# Image_sensor.net
KiCad netlist of a schematic drawn in EasyEDA Pro
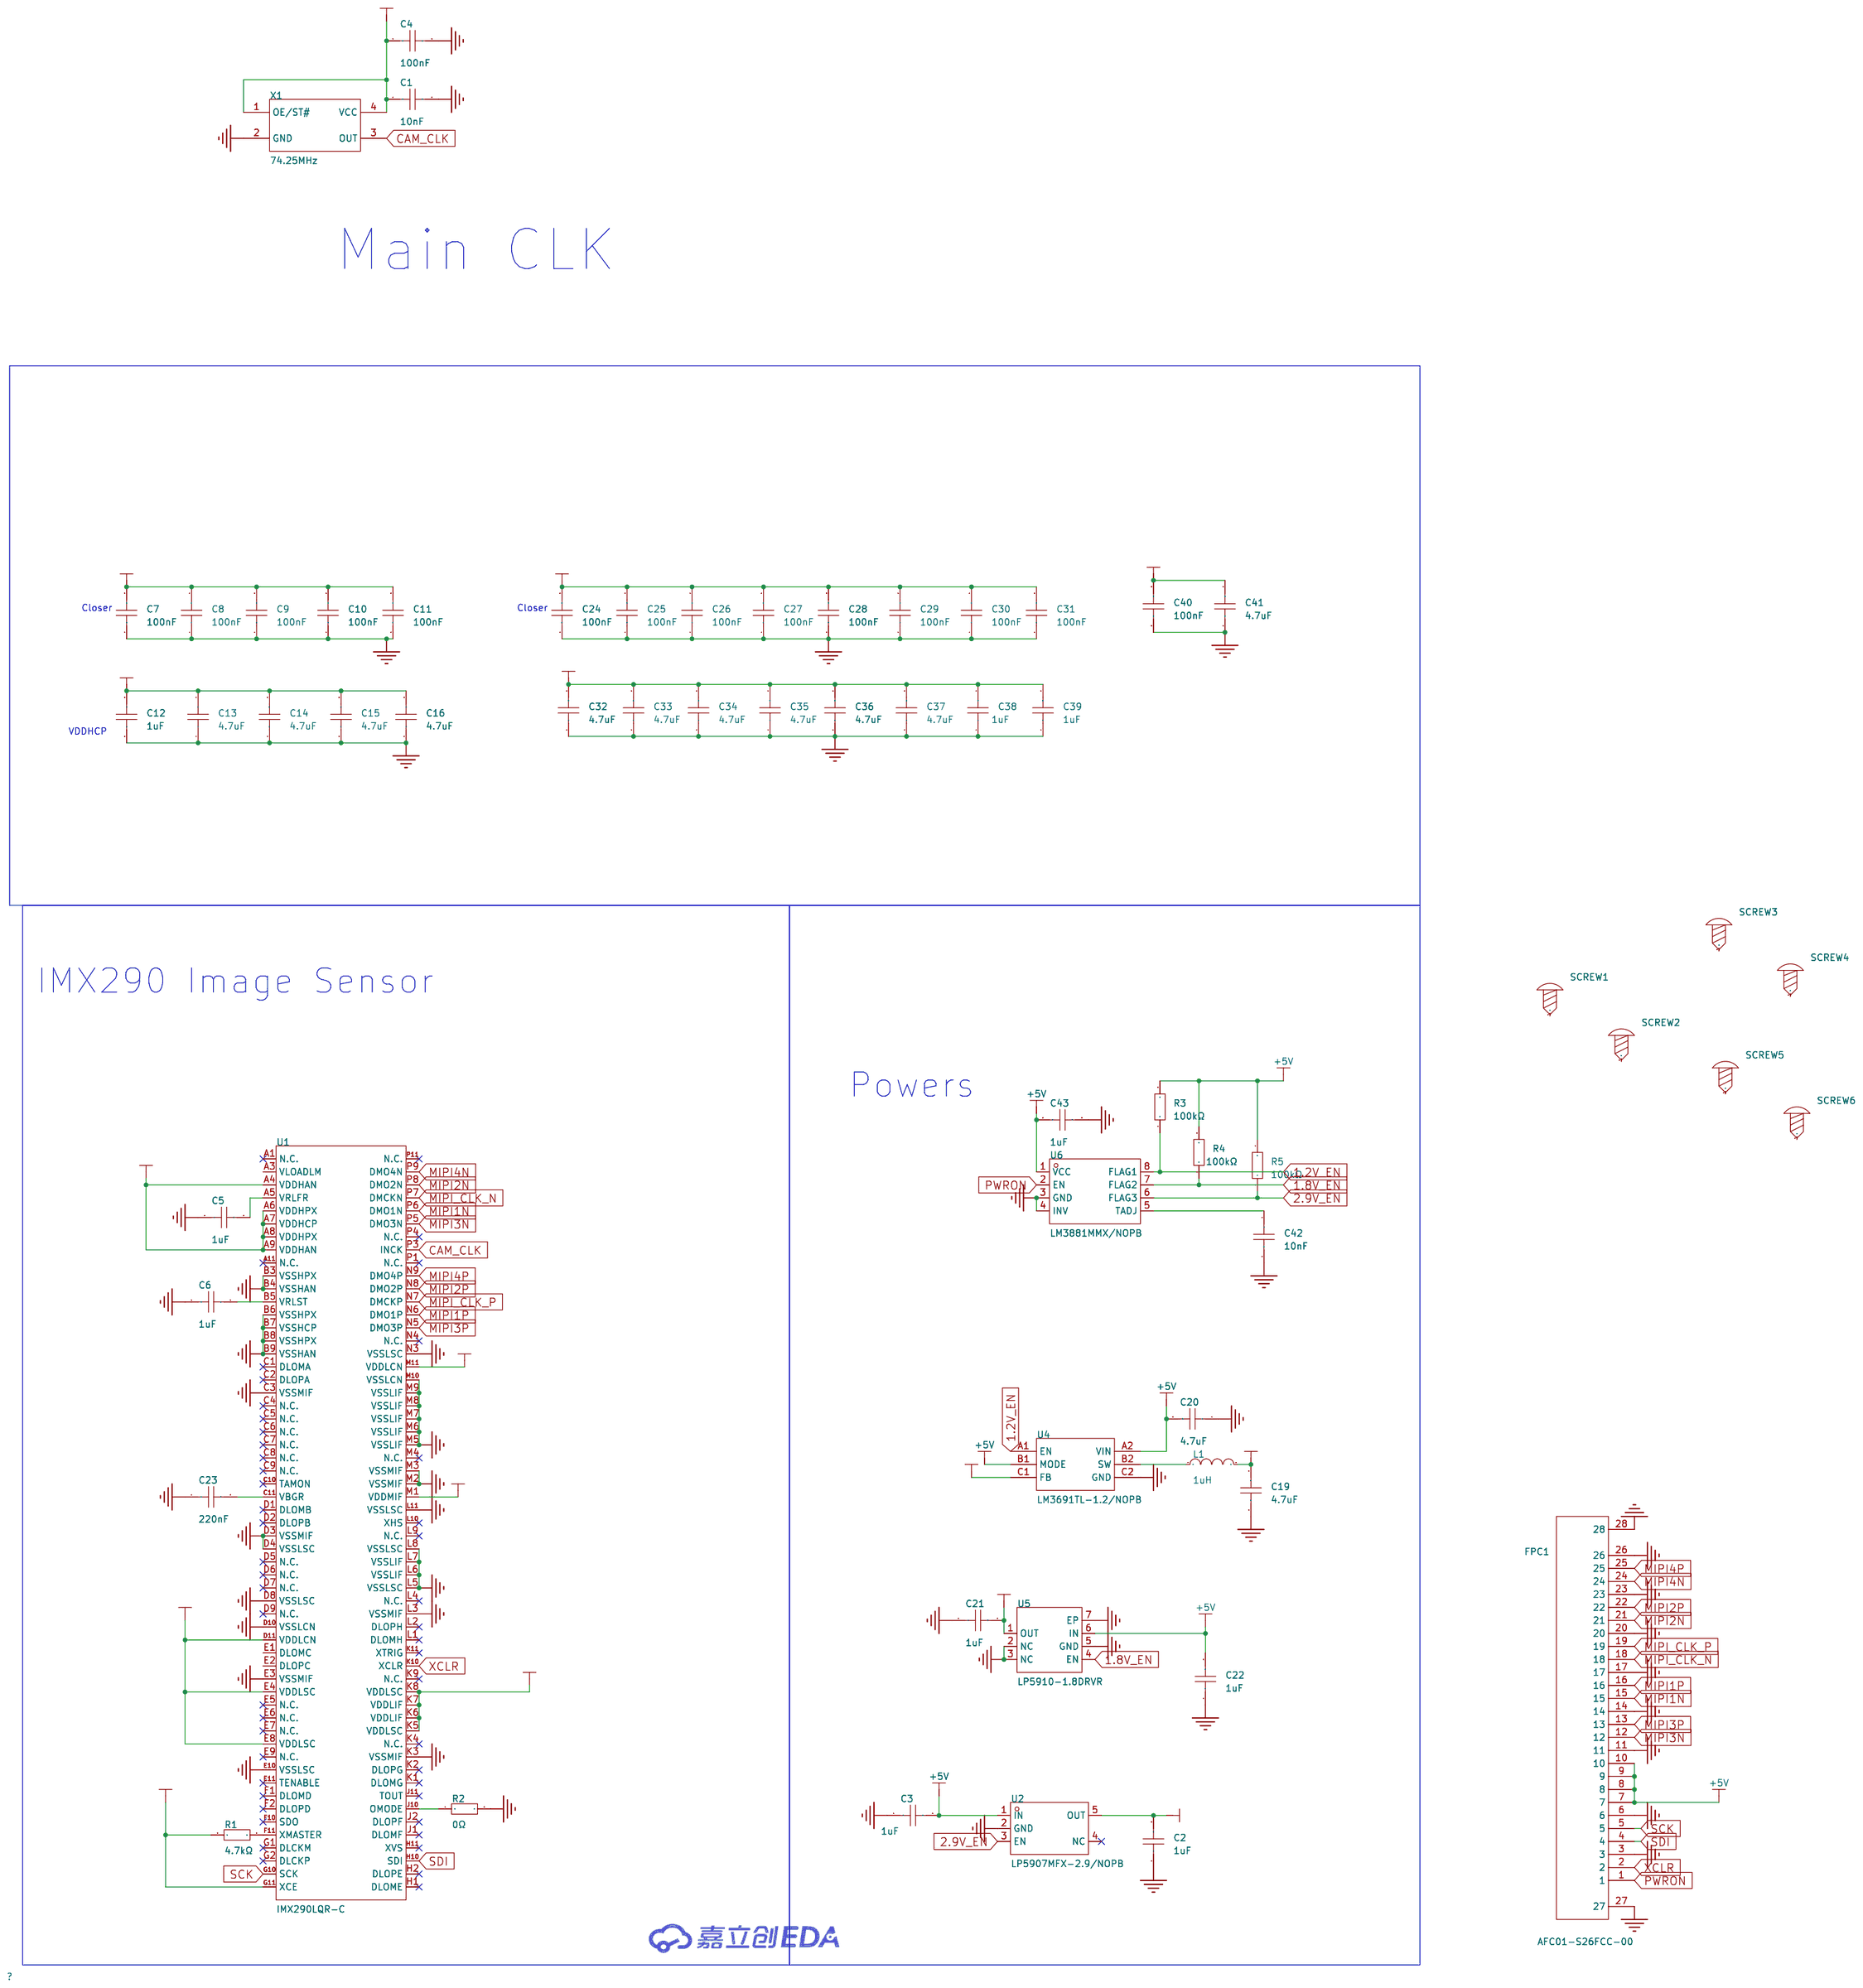
[diagram p0: schematic sheet]

(export (version "E")
  (design (tool "Eeschema 10.0.6"))
  (components
    (comp (ref "C1")
      (value "10nF")
      (footprint "easyedapro:C0603")
      (fields
        (field (name "Manufacturer Part") "CL02A103KQ2NNXC")
        (field (name "Manufacturer") "SAMSUNG(三星)")
      )
      (libsource (lib "easyedapro") (part "Capacitance"))
    )
    (comp (ref "C2")
      (value "1uF")
      (footprint "easyedapro:C0603")
      (fields
        (field (name "Manufacturer Part") "CL03A105KP3NSNC")
        (field (name "Manufacturer") "SAMSUNG(三星)")
      )
      (libsource (lib "easyedapro") (part "Capacitance"))
    )
    (comp (ref "C3")
      (value "1uF")
      (footprint "easyedapro:C0603")
      (fields
        (field (name "Manufacturer Part") "CL03A105KP3NSNC")
        (field (name "Manufacturer") "SAMSUNG(三星)")
      )
      (libsource (lib "easyedapro") (part "Capacitance"))
    )
    (comp (ref "C4")
      (value "100nF")
      (footprint "easyedapro:C0603")
      (fields
        (field (name "Manufacturer Part") "GRM022R60J104KE15D")
        (field (name "Manufacturer") "muRata(村田)")
      )
      (libsource (lib "easyedapro") (part "Capacitance"))
    )
    (comp (ref "C5")
      (value "1uF")
      (footprint "easyedapro:C0603")
      (fields
        (field (name "Manufacturer Part") "CL03A105KP3NSNC")
        (field (name "Manufacturer") "SAMSUNG(三星)")
      )
      (libsource (lib "easyedapro") (part "Capacitance"))
    )
    (comp (ref "C6")
      (value "1uF")
      (footprint "easyedapro:C0603")
      (fields
        (field (name "Manufacturer Part") "CL03A105KP3NSNC")
        (field (name "Manufacturer") "SAMSUNG(三星)")
      )
      (libsource (lib "easyedapro") (part "Capacitance"))
    )
    (comp (ref "C7")
      (value "100nF")
      (footprint "easyedapro:C0603")
      (fields
        (field (name "Manufacturer Part") "GRM022R60J104KE15D")
        (field (name "Manufacturer") "muRata(村田)")
      )
      (libsource (lib "easyedapro") (part "Capacitance"))
    )
    (comp (ref "C8")
      (value "100nF")
      (footprint "easyedapro:C0603")
      (fields
        (field (name "Manufacturer Part") "GRM022R60J104KE15D")
        (field (name "Manufacturer") "muRata(村田)")
      )
      (libsource (lib "easyedapro") (part "Capacitance"))
    )
    (comp (ref "C9")
      (value "100nF")
      (footprint "easyedapro:C0603")
      (fields
        (field (name "Manufacturer Part") "GRM022R60J104KE15D")
        (field (name "Manufacturer") "muRata(村田)")
      )
      (libsource (lib "easyedapro") (part "Capacitance"))
    )
    (comp (ref "C10")
      (value "100nF")
      (footprint "easyedapro:C0603")
      (fields
        (field (name "Manufacturer Part") "GRM022R60J104KE15D")
        (field (name "Manufacturer") "muRata(村田)")
      )
      (libsource (lib "easyedapro") (part "Capacitance"))
    )
    (comp (ref "C11")
      (value "100nF")
      (footprint "easyedapro:C0603")
      (fields
        (field (name "Manufacturer Part") "GRM022R60J104KE15D")
        (field (name "Manufacturer") "muRata(村田)")
      )
      (libsource (lib "easyedapro") (part "Capacitance"))
    )
    (comp (ref "C12")
      (value "1uF")
      (footprint "easyedapro:C0603")
      (fields
        (field (name "Manufacturer Part") "CL03A105KP3NSNC")
        (field (name "Manufacturer") "SAMSUNG(三星)")
      )
      (libsource (lib "easyedapro") (part "Capacitance"))
    )
    (comp (ref "C13")
      (value "4.7uF")
      (footprint "easyedapro:C0603")
      (fields
        (field (name "Manufacturer Part") "GRM035R60J475ME15D")
        (field (name "Manufacturer") "muRata(村田)")
      )
      (libsource (lib "easyedapro") (part "Capacitance"))
    )
    (comp (ref "C14")
      (value "4.7uF")
      (footprint "easyedapro:C0603")
      (fields
        (field (name "Manufacturer Part") "GRM035R60J475ME15D")
        (field (name "Manufacturer") "muRata(村田)")
      )
      (libsource (lib "easyedapro") (part "Capacitance"))
    )
    (comp (ref "C15")
      (value "4.7uF")
      (footprint "easyedapro:C0603")
      (fields
        (field (name "Manufacturer Part") "GRM035R60J475ME15D")
        (field (name "Manufacturer") "muRata(村田)")
      )
      (libsource (lib "easyedapro") (part "Capacitance"))
    )
    (comp (ref "C16")
      (value "4.7uF")
      (footprint "easyedapro:C0603")
      (fields
        (field (name "Manufacturer Part") "GRM035R60J475ME15D")
        (field (name "Manufacturer") "muRata(村田)")
      )
      (libsource (lib "easyedapro") (part "Capacitance"))
    )
    (comp (ref "C19")
      (value "4.7uF")
      (footprint "easyedapro:C0603")
      (fields
        (field (name "Manufacturer Part") "GRM035R60J475ME15D")
        (field (name "Manufacturer") "muRata(村田)")
      )
      (libsource (lib "easyedapro") (part "Capacitance"))
    )
    (comp (ref "C20")
      (value "4.7uF")
      (footprint "easyedapro:C0603")
      (fields
        (field (name "Manufacturer Part") "GRM035R60J475ME15D")
        (field (name "Manufacturer") "muRata(村田)")
      )
      (libsource (lib "easyedapro") (part "Capacitance"))
    )
    (comp (ref "C21")
      (value "1uF")
      (footprint "easyedapro:C0603")
      (fields
        (field (name "Manufacturer Part") "CL03A105KP3NSNC")
        (field (name "Manufacturer") "SAMSUNG(三星)")
      )
      (libsource (lib "easyedapro") (part "Capacitance"))
    )
    (comp (ref "C22")
      (value "1uF")
      (footprint "easyedapro:C0603")
      (fields
        (field (name "Manufacturer Part") "CL03A105KP3NSNC")
        (field (name "Manufacturer") "SAMSUNG(三星)")
      )
      (libsource (lib "easyedapro") (part "Capacitance"))
    )
    (comp (ref "C23")
      (value "220nF")
      (footprint "easyedapro:C0603")
      (fields
        (field (name "Manufacturer Part") "GRM022R60J224KE14D")
        (field (name "Manufacturer") "muRata(村田)")
      )
      (libsource (lib "easyedapro") (part "Capacitance"))
    )
    (comp (ref "C24")
      (value "100nF")
      (footprint "easyedapro:C0603")
      (fields
        (field (name "Manufacturer Part") "GRM022R60J104KE15D")
        (field (name "Manufacturer") "muRata(村田)")
      )
      (libsource (lib "easyedapro") (part "Capacitance"))
    )
    (comp (ref "C25")
      (value "100nF")
      (footprint "easyedapro:C0603")
      (fields
        (field (name "Manufacturer Part") "GRM022R60J104KE15D")
        (field (name "Manufacturer") "muRata(村田)")
      )
      (libsource (lib "easyedapro") (part "Capacitance"))
    )
    (comp (ref "C26")
      (value "100nF")
      (footprint "easyedapro:C0603")
      (fields
        (field (name "Manufacturer Part") "GRM022R60J104KE15D")
        (field (name "Manufacturer") "muRata(村田)")
      )
      (libsource (lib "easyedapro") (part "Capacitance"))
    )
    (comp (ref "C27")
      (value "100nF")
      (footprint "easyedapro:C0603")
      (fields
        (field (name "Manufacturer Part") "GRM022R60J104KE15D")
        (field (name "Manufacturer") "muRata(村田)")
      )
      (libsource (lib "easyedapro") (part "Capacitance"))
    )
    (comp (ref "C28")
      (value "100nF")
      (footprint "easyedapro:C0603")
      (fields
        (field (name "Manufacturer Part") "GRM022R60J104KE15D")
        (field (name "Manufacturer") "muRata(村田)")
      )
      (libsource (lib "easyedapro") (part "Capacitance"))
    )
    (comp (ref "C29")
      (value "100nF")
      (footprint "easyedapro:C0603")
      (fields
        (field (name "Manufacturer Part") "GRM022R60J104KE15D")
        (field (name "Manufacturer") "muRata(村田)")
      )
      (libsource (lib "easyedapro") (part "Capacitance"))
    )
    (comp (ref "C30")
      (value "100nF")
      (footprint "easyedapro:C0603")
      (fields
        (field (name "Manufacturer Part") "GRM022R60J104KE15D")
        (field (name "Manufacturer") "muRata(村田)")
      )
      (libsource (lib "easyedapro") (part "Capacitance"))
    )
    (comp (ref "C31")
      (value "100nF")
      (footprint "easyedapro:C0603")
      (fields
        (field (name "Manufacturer Part") "GRM022R60J104KE15D")
        (field (name "Manufacturer") "muRata(村田)")
      )
      (libsource (lib "easyedapro") (part "Capacitance"))
    )
    (comp (ref "C32")
      (value "4.7uF")
      (footprint "easyedapro:C0603")
      (fields
        (field (name "Manufacturer Part") "GRM035R60J475ME15D")
        (field (name "Manufacturer") "muRata(村田)")
      )
      (libsource (lib "easyedapro") (part "Capacitance"))
    )
    (comp (ref "C33")
      (value "4.7uF")
      (footprint "easyedapro:C0603")
      (fields
        (field (name "Manufacturer Part") "GRM035R60J475ME15D")
        (field (name "Manufacturer") "muRata(村田)")
      )
      (libsource (lib "easyedapro") (part "Capacitance"))
    )
    (comp (ref "C34")
      (value "4.7uF")
      (footprint "easyedapro:C0603")
      (fields
        (field (name "Manufacturer Part") "GRM035R60J475ME15D")
        (field (name "Manufacturer") "muRata(村田)")
      )
      (libsource (lib "easyedapro") (part "Capacitance"))
    )
    (comp (ref "C35")
      (value "4.7uF")
      (footprint "easyedapro:C0603")
      (fields
        (field (name "Manufacturer Part") "GRM035R60J475ME15D")
        (field (name "Manufacturer") "muRata(村田)")
      )
      (libsource (lib "easyedapro") (part "Capacitance"))
    )
    (comp (ref "C36")
      (value "4.7uF")
      (footprint "easyedapro:C0603")
      (fields
        (field (name "Manufacturer Part") "GRM035R60J475ME15D")
        (field (name "Manufacturer") "muRata(村田)")
      )
      (libsource (lib "easyedapro") (part "Capacitance"))
    )
    (comp (ref "C37")
      (value "4.7uF")
      (footprint "easyedapro:C0603")
      (fields
        (field (name "Manufacturer Part") "GRM035R60J475ME15D")
        (field (name "Manufacturer") "muRata(村田)")
      )
      (libsource (lib "easyedapro") (part "Capacitance"))
    )
    (comp (ref "C38")
      (value "1uF")
      (footprint "easyedapro:C0603")
      (fields
        (field (name "Manufacturer Part") "CL03A105KP3NSNC")
        (field (name "Manufacturer") "SAMSUNG(三星)")
      )
      (libsource (lib "easyedapro") (part "Capacitance"))
    )
    (comp (ref "C39")
      (value "1uF")
      (footprint "easyedapro:C0603")
      (fields
        (field (name "Manufacturer Part") "CL03A105KP3NSNC")
        (field (name "Manufacturer") "SAMSUNG(三星)")
      )
      (libsource (lib "easyedapro") (part "Capacitance"))
    )
    (comp (ref "C40")
      (value "100nF")
      (footprint "easyedapro:C0603")
      (fields
        (field (name "Manufacturer Part") "GRM022R60J104KE15D")
        (field (name "Manufacturer") "muRata(村田)")
      )
      (libsource (lib "easyedapro") (part "Capacitance"))
    )
    (comp (ref "C41")
      (value "4.7uF")
      (footprint "easyedapro:C0603")
      (fields
        (field (name "Manufacturer Part") "GRM035R60J475ME15D")
        (field (name "Manufacturer") "muRata(村田)")
      )
      (libsource (lib "easyedapro") (part "Capacitance"))
    )
    (comp (ref "C42")
      (value "10nF")
      (footprint "easyedapro:C0603")
      (fields
        (field (name "Manufacturer Part") "GRM033R71A103KA01D")
        (field (name "Manufacturer") "muRata(村田)")
      )
      (libsource (lib "easyedapro") (part "Capacitance"))
    )
    (comp (ref "C43")
      (value "1uF")
      (footprint "easyedapro:C0603")
      (fields
        (field (name "Manufacturer Part") "GRM033R61A105ME44D")
        (field (name "Manufacturer") "muRata(村田)")
      )
      (libsource (lib "easyedapro") (part "Capacitance"))
    )
    (comp (ref "FPC1")
      (value "AFC01-S26FCC-00")
      (footprint "easyedapro:FPC-SMD_AFC01-S26FCC-00")
      (description "锁定特性:翻盖式;触点类型:下接;触点数量:26P;间距:0.5mm;安装类型:卧贴;")
      (fields (field (name "Manufacturer") "JS(钜硕电子)"))
      (libsource (lib "easyedapro") (part "AFC01-S26FCC-00"))
    )
    (comp (ref "L1")
      (value "1uH")
      (footprint "easyedapro:L0603")
      (fields
        (field (name "Manufacturer Part") "MPH201610S1R0MT")
        (field (name "Manufacturer") "Sunlord(顺络)")
      )
      (libsource (lib "easyedapro") (part "SDFL1608S100KTF"))
    )
    (comp (ref "R1")
      (value "4.7kΩ")
      (footprint "easyedapro:R0603")
      (fields
        (field (name "Manufacturer Part") "0201WMF4701TEE")
        (field (name "Manufacturer") "UNI-ROYAL(厚声)")
      )
      (libsource (lib "easyedapro") (part "电阻"))
    )
    (comp (ref "R2")
      (value "0Ω")
      (footprint "easyedapro:R0603")
      (fields
        (field (name "Manufacturer Part") "0603WAF0000T5E")
        (field (name "Manufacturer") "UNI-ROYAL(厚声)")
      )
      (libsource (lib "easyedapro") (part "电阻"))
    )
    (comp (ref "R3")
      (value "100kΩ")
      (footprint "easyedapro:R0603")
      (fields
        (field (name "Manufacturer Part") "0201WMF1003TEE")
        (field (name "Manufacturer") "UNI-ROYAL(厚声)")
      )
      (libsource (lib "easyedapro") (part "电阻"))
    )
    (comp (ref "R4")
      (value "100kΩ")
      (footprint "easyedapro:R0603")
      (fields
        (field (name "Manufacturer Part") "0201WMF1003TEE")
        (field (name "Manufacturer") "UNI-ROYAL(厚声)")
      )
      (libsource (lib "easyedapro") (part "电阻"))
    )
    (comp (ref "R5")
      (value "100kΩ")
      (footprint "easyedapro:R0603")
      (fields
        (field (name "Manufacturer Part") "0201WMF1003TEE")
        (field (name "Manufacturer") "UNI-ROYAL(厚声)")
      )
      (libsource (lib "easyedapro") (part "电阻"))
    )
    (comp (ref "SCREW1")
      (value "~")
      (footprint "easyedapro:M2螺丝")
      (libsource (lib "easyedapro") (part "螺丝孔"))
    )
    (comp (ref "SCREW2")
      (value "~")
      (footprint "easyedapro:M2螺丝")
      (libsource (lib "easyedapro") (part "螺丝孔"))
    )
    (comp (ref "SCREW3")
      (value "~")
      (footprint "easyedapro:M2螺丝")
      (libsource (lib "easyedapro") (part "螺丝孔"))
    )
    (comp (ref "SCREW4")
      (value "~")
      (footprint "easyedapro:M2螺丝")
      (libsource (lib "easyedapro") (part "螺丝孔"))
    )
    (comp (ref "SCREW5")
      (value "~")
      (footprint "easyedapro:M2螺丝")
      (libsource (lib "easyedapro") (part "螺丝孔"))
    )
    (comp (ref "SCREW6")
      (value "~")
      (footprint "easyedapro:M2螺丝")
      (libsource (lib "easyedapro") (part "螺丝孔"))
    )
    (comp (ref "U1")
      (value "IMX290LQR-C")
      (footprint "easyedapro:LGA-110_L12.0-W9.3-P0.80-BL_IMX291LQR-C")
      (fields (field (name "Manufacturer") "Sony(索尼)"))
      (libsource (lib "easyedapro") (part "IMX290LQR-C"))
    )
    (comp (ref "U2")
      (value "LP5907MFX-2.9/NOPB")
      (footprint "easyedapro:SOT-23-5_L2.9-W1.6-P0.95-LS2.8-BR")
      (description "输出类型:固定;最大输入电压:5.5V;输出电压:2.9V;输出电流:250mA;输出极性:正极;")
      (fields (field (name "Manufacturer") "TI(德州仪器)"))
      (libsource (lib "easyedapro") (part "LP5907MFX-2.9/NOPB"))
    )
    (comp (ref "U4")
      (value "LM3691TL-1.2/NOPB")
      (footprint "easyedapro:DSBGA-6_L1.5-W1.3-R2-C3-P0.50-BL")
      (description "功能类型:降压型;输出类型:固定;输入电压:2.3V~5.5V;输出电压:1.2V;输出电流:1A;")
      (fields (field (name "Manufacturer") "TI(德州仪器)"))
      (libsource (lib "easyedapro") (part "LM3691TL-1.2/NOPB"))
    )
    (comp (ref "U5")
      (value "LP5910-1.8DRVR")
      (footprint "easyedapro:WSON-6_L2.0-W2.0-P0.65-TL-EP")
      (description "输出类型:固定;工作电压:3.3V;输出电压:1.8V;输出电流:300mA;输出极性:正极;")
      (fields (field (name "Manufacturer") "TI(德州仪器)"))
      (libsource (lib "easyedapro") (part "LP5910-1.8DRVR"))
    )
    (comp (ref "U6")
      (value "LM3881MMX/NOPB")
      (footprint "easyedapro:VSSOP-8_L3.0-W3.0-P0.65-LS5.0-BL")
      (description "工作电压:2.7V~5.5V;复位有效电平:-;受监控电压数:3;复位超时:10.8ms;")
      (fields (field (name "Manufacturer") "TI(德州仪器)"))
      (libsource (lib "easyedapro") (part "LM3881MMX/NOPB"))
    )
    (comp (ref "X1")
      (value "74.25MHz")
      (footprint "easyedapro:OSC-SMD_4P-L7.0-W5.0-BL_SG7050")
      (description "频率:74.25MHz;工作电压:1.6V~3.6V;工作电流:11mA;频率稳定度:±50ppm;")
      (fields (field (name "Manufacturer Part") "X1G0044810047") (field (name "Manufacturer") "EPSON(爱普生)"))
      (libsource (lib "easyedapro") (part "X1G004481004700"))
    )
  )
  (nets
    (net (code "1") (name "+5V") (class "Default")
      (node (ref "C20") (pin "2") (pinfunction "2_2") (pintype "input"))
      (node (ref "C22") (pin "2") (pinfunction "2_2") (pintype "input"))
      (node (ref "C3") (pin "2") (pinfunction "2_2") (pintype "input"))
      (node (ref "C43") (pin "1") (pinfunction "1_1") (pintype "input"))
      (node (ref "FPC1") (pin "10") (pinfunction "10_10") (pintype "unspecified"))
      (node (ref "FPC1") (pin "7") (pinfunction "7_7") (pintype "unspecified"))
      (node (ref "FPC1") (pin "8") (pinfunction "8_8") (pintype "unspecified"))
      (node (ref "FPC1") (pin "9") (pinfunction "9_9") (pintype "unspecified"))
      (node (ref "R3") (pin "2") (pinfunction "2_2") (pintype "input"))
      (node (ref "R4") (pin "2") (pinfunction "2_2") (pintype "input"))
      (node (ref "R5") (pin "2") (pinfunction "2_2") (pintype "input"))
      (node (ref "U2") (pin "1") (pinfunction "IN_1") (pintype "unspecified"))
      (node (ref "U4") (pin "A2") (pinfunction "VIN_A2") (pintype "unspecified"))
      (node (ref "U4") (pin "B1") (pinfunction "MODE_B1") (pintype "unspecified"))
      (node (ref "U5") (pin "6") (pinfunction "IN_6") (pintype "unspecified"))
      (node (ref "U6") (pin "1") (pinfunction "VCC_1") (pintype "unspecified"))
    )
    (net (code "2") (name "1.2V") (class "Default")
      (node (ref "C19") (pin "2") (pinfunction "2_2") (pintype "input"))
      (node (ref "C24") (pin "2") (pinfunction "2_2") (pintype "input"))
      (node (ref "C25") (pin "2") (pinfunction "2_2") (pintype "input"))
      (node (ref "C26") (pin "2") (pinfunction "2_2") (pintype "input"))
      (node (ref "C27") (pin "2") (pinfunction "2_2") (pintype "input"))
      (node (ref "C28") (pin "2") (pinfunction "2_2") (pintype "input"))
      (node (ref "C29") (pin "2") (pinfunction "2_2") (pintype "input"))
      (node (ref "C30") (pin "2") (pinfunction "2_2") (pintype "input"))
      (node (ref "C31") (pin "2") (pinfunction "2_2") (pintype "input"))
      (node (ref "C32") (pin "2") (pinfunction "2_2") (pintype "input"))
      (node (ref "C33") (pin "2") (pinfunction "2_2") (pintype "input"))
      (node (ref "C34") (pin "2") (pinfunction "2_2") (pintype "input"))
      (node (ref "C35") (pin "2") (pinfunction "2_2") (pintype "input"))
      (node (ref "C36") (pin "2") (pinfunction "2_2") (pintype "input"))
      (node (ref "C37") (pin "2") (pinfunction "2_2") (pintype "input"))
      (node (ref "C38") (pin "2") (pinfunction "2_2") (pintype "input"))
      (node (ref "C39") (pin "2") (pinfunction "2_2") (pintype "input"))
      (node (ref "L1") (pin "2") (pinfunction "2_2") (pintype "unspecified"))
      (node (ref "U1") (pin "D11") (pinfunction "VDDLCN_D11") (pintype "unspecified"))
      (node (ref "U1") (pin "E4") (pinfunction "VDDLSC_E4") (pintype "unspecified"))
      (node (ref "U1") (pin "E8") (pinfunction "VDDLSC_E8") (pintype "unspecified"))
      (node (ref "U1") (pin "K5") (pinfunction "VDDLSC_K5") (pintype "unspecified"))
      (node (ref "U1") (pin "K6") (pinfunction "VDDLIF_K6") (pintype "unspecified"))
      (node (ref "U1") (pin "K7") (pinfunction "VDDLIF_K7") (pintype "unspecified"))
      (node (ref "U1") (pin "K8") (pinfunction "VDDLSC_K8") (pintype "unspecified"))
      (node (ref "U1") (pin "M11") (pinfunction "VDDLCN_M11") (pintype "unspecified"))
      (node (ref "U4") (pin "C1") (pinfunction "FB_C1") (pintype "unspecified"))
    )
    (net (code "3") (name "1.2V_EN") (class "Default")
      (node (ref "R3") (pin "1") (pinfunction "1_1") (pintype "input"))
      (node (ref "U4") (pin "A1") (pinfunction "EN_A1") (pintype "unspecified"))
      (node (ref "U6") (pin "8") (pinfunction "FLAG1_8") (pintype "unspecified"))
    )
    (net (code "4") (name "1.8V") (class "Default")
      (node (ref "C21") (pin "2") (pinfunction "2_2") (pintype "input"))
      (node (ref "C40") (pin "2") (pinfunction "2_2") (pintype "input"))
      (node (ref "C41") (pin "2") (pinfunction "2_2") (pintype "input"))
      (node (ref "R1") (pin "1") (pinfunction "1_1") (pintype "input"))
      (node (ref "U1") (pin "G11") (pinfunction "XCE_G11") (pintype "unspecified"))
      (node (ref "U1") (pin "M1") (pinfunction "VDDMIF_M1") (pintype "unspecified"))
      (node (ref "U5") (pin "1") (pinfunction "OUT_1") (pintype "unspecified"))
    )
    (net (code "5") (name "1.8V_EN") (class "Default")
      (node (ref "R4") (pin "1") (pinfunction "1_1") (pintype "input"))
      (node (ref "U5") (pin "4") (pinfunction "EN_4") (pintype "unspecified"))
      (node (ref "U6") (pin "7") (pinfunction "FLAG2_7") (pintype "unspecified"))
    )
    (net (code "6") (name "2.9V") (class "Default")
      (node (ref "C1") (pin "1") (pinfunction "1_1") (pintype "input"))
      (node (ref "C10") (pin "2") (pinfunction "2_2") (pintype "input"))
      (node (ref "C11") (pin "2") (pinfunction "2_2") (pintype "input"))
      (node (ref "C12") (pin "2") (pinfunction "2_2") (pintype "input"))
      (node (ref "C13") (pin "2") (pinfunction "2_2") (pintype "input"))
      (node (ref "C14") (pin "2") (pinfunction "2_2") (pintype "input"))
      (node (ref "C15") (pin "2") (pinfunction "2_2") (pintype "input"))
      (node (ref "C16") (pin "2") (pinfunction "2_2") (pintype "input"))
      (node (ref "C2") (pin "2") (pinfunction "2_2") (pintype "input"))
      (node (ref "C4") (pin "1") (pinfunction "1_1") (pintype "input"))
      (node (ref "C7") (pin "2") (pinfunction "2_2") (pintype "input"))
      (node (ref "C8") (pin "2") (pinfunction "2_2") (pintype "input"))
      (node (ref "C9") (pin "2") (pinfunction "2_2") (pintype "input"))
      (node (ref "U1") (pin "A4") (pinfunction "VDDHAN_A4") (pintype "unspecified"))
      (node (ref "U1") (pin "A6") (pinfunction "VDDHPX_A6") (pintype "unspecified"))
      (node (ref "U1") (pin "A7") (pinfunction "VDDHCP_A7") (pintype "unspecified"))
      (node (ref "U1") (pin "A8") (pinfunction "VDDHPX_A8") (pintype "unspecified"))
      (node (ref "U1") (pin "A9") (pinfunction "VDDHAN_A9") (pintype "unspecified"))
      (node (ref "U2") (pin "5") (pinfunction "OUT_5") (pintype "unspecified"))
      (node (ref "X1") (pin "1") (pinfunction "OE/ST#_1") (pintype "unspecified"))
      (node (ref "X1") (pin "4") (pinfunction "VCC_4") (pintype "unspecified"))
    )
    (net (code "7") (name "2.9V_EN") (class "Default")
      (node (ref "R5") (pin "1") (pinfunction "1_1") (pintype "input"))
      (node (ref "U2") (pin "3") (pinfunction "EN_3") (pintype "unspecified"))
      (node (ref "U6") (pin "6") (pinfunction "FLAG3_6") (pintype "unspecified"))
    )
    (net (code "8") (name "CAM_CLK") (class "Default")
      (node (ref "U1") (pin "P3") (pinfunction "INCK_P3") (pintype "unspecified"))
      (node (ref "X1") (pin "3") (pinfunction "OUT_3") (pintype "unspecified"))
    )
    (net (code "9") (name "GND") (class "Default")
      (node (ref "C1") (pin "2") (pinfunction "2_2") (pintype "input"))
      (node (ref "C10") (pin "1") (pinfunction "1_1") (pintype "input"))
      (node (ref "C11") (pin "1") (pinfunction "1_1") (pintype "input"))
      (node (ref "C12") (pin "1") (pinfunction "1_1") (pintype "input"))
      (node (ref "C13") (pin "1") (pinfunction "1_1") (pintype "input"))
      (node (ref "C14") (pin "1") (pinfunction "1_1") (pintype "input"))
      (node (ref "C15") (pin "1") (pinfunction "1_1") (pintype "input"))
      (node (ref "C16") (pin "1") (pinfunction "1_1") (pintype "input"))
      (node (ref "C19") (pin "1") (pinfunction "1_1") (pintype "input"))
      (node (ref "C2") (pin "1") (pinfunction "1_1") (pintype "input"))
      (node (ref "C20") (pin "1") (pinfunction "1_1") (pintype "input"))
      (node (ref "C21") (pin "1") (pinfunction "1_1") (pintype "input"))
      (node (ref "C22") (pin "1") (pinfunction "1_1") (pintype "input"))
      (node (ref "C23") (pin "1") (pinfunction "1_1") (pintype "input"))
      (node (ref "C24") (pin "1") (pinfunction "1_1") (pintype "input"))
      (node (ref "C25") (pin "1") (pinfunction "1_1") (pintype "input"))
      (node (ref "C26") (pin "1") (pinfunction "1_1") (pintype "input"))
      (node (ref "C27") (pin "1") (pinfunction "1_1") (pintype "input"))
      (node (ref "C28") (pin "1") (pinfunction "1_1") (pintype "input"))
      (node (ref "C29") (pin "1") (pinfunction "1_1") (pintype "input"))
      (node (ref "C3") (pin "1") (pinfunction "1_1") (pintype "input"))
      (node (ref "C30") (pin "1") (pinfunction "1_1") (pintype "input"))
      (node (ref "C31") (pin "1") (pinfunction "1_1") (pintype "input"))
      (node (ref "C32") (pin "1") (pinfunction "1_1") (pintype "input"))
      (node (ref "C33") (pin "1") (pinfunction "1_1") (pintype "input"))
      (node (ref "C34") (pin "1") (pinfunction "1_1") (pintype "input"))
      (node (ref "C35") (pin "1") (pinfunction "1_1") (pintype "input"))
      (node (ref "C36") (pin "1") (pinfunction "1_1") (pintype "input"))
      (node (ref "C37") (pin "1") (pinfunction "1_1") (pintype "input"))
      (node (ref "C38") (pin "1") (pinfunction "1_1") (pintype "input"))
      (node (ref "C39") (pin "1") (pinfunction "1_1") (pintype "input"))
      (node (ref "C4") (pin "2") (pinfunction "2_2") (pintype "input"))
      (node (ref "C40") (pin "1") (pinfunction "1_1") (pintype "input"))
      (node (ref "C41") (pin "1") (pinfunction "1_1") (pintype "input"))
      (node (ref "C42") (pin "2") (pinfunction "2_2") (pintype "input"))
      (node (ref "C43") (pin "2") (pinfunction "2_2") (pintype "input"))
      (node (ref "C5") (pin "1") (pinfunction "1_1") (pintype "input"))
      (node (ref "C6") (pin "1") (pinfunction "1_1") (pintype "input"))
      (node (ref "C7") (pin "1") (pinfunction "1_1") (pintype "input"))
      (node (ref "C8") (pin "1") (pinfunction "1_1") (pintype "input"))
      (node (ref "C9") (pin "1") (pinfunction "1_1") (pintype "input"))
      (node (ref "FPC1") (pin "11") (pinfunction "11_11") (pintype "unspecified"))
      (node (ref "FPC1") (pin "14") (pinfunction "14_14") (pintype "unspecified"))
      (node (ref "FPC1") (pin "17") (pinfunction "17_17") (pintype "unspecified"))
      (node (ref "FPC1") (pin "20") (pinfunction "20_20") (pintype "unspecified"))
      (node (ref "FPC1") (pin "23") (pinfunction "23_23") (pintype "unspecified"))
      (node (ref "FPC1") (pin "26") (pinfunction "26_26") (pintype "unspecified"))
      (node (ref "FPC1") (pin "27") (pinfunction "27_27") (pintype "unspecified"))
      (node (ref "FPC1") (pin "28") (pinfunction "28_28") (pintype "unspecified"))
      (node (ref "FPC1") (pin "3") (pinfunction "3_3") (pintype "unspecified"))
      (node (ref "FPC1") (pin "6") (pinfunction "6_6") (pintype "unspecified"))
      (node (ref "R2") (pin "2") (pinfunction "2_2") (pintype "input"))
      (node (ref "U1") (pin "B3") (pinfunction "VSSHPX_B3") (pintype "unspecified"))
      (node (ref "U1") (pin "B4") (pinfunction "VSSHAN_B4") (pintype "unspecified"))
      (node (ref "U1") (pin "B6") (pinfunction "VSSHPX_B6") (pintype "unspecified"))
      (node (ref "U1") (pin "B7") (pinfunction "VSSHCP_B7") (pintype "unspecified"))
      (node (ref "U1") (pin "B8") (pinfunction "VSSHPX_B8") (pintype "unspecified"))
      (node (ref "U1") (pin "B9") (pinfunction "VSSHAN_B9") (pintype "unspecified"))
      (node (ref "U1") (pin "C3") (pinfunction "VSSMIF_C3") (pintype "unspecified"))
      (node (ref "U1") (pin "D10") (pinfunction "VSSLCN_D10") (pintype "unspecified"))
      (node (ref "U1") (pin "D3") (pinfunction "VSSMIF_D3") (pintype "unspecified"))
      (node (ref "U1") (pin "D4") (pinfunction "VSSLSC_D4") (pintype "unspecified"))
      (node (ref "U1") (pin "D8") (pinfunction "VSSLSC_D8") (pintype "unspecified"))
      (node (ref "U1") (pin "E10") (pinfunction "VSSLSC_E10") (pintype "unspecified"))
      (node (ref "U1") (pin "E3") (pinfunction "VSSMIF_E3") (pintype "unspecified"))
      (node (ref "U1") (pin "K3") (pinfunction "VSSMIF_K3") (pintype "unspecified"))
      (node (ref "U1") (pin "L11") (pinfunction "VSSLSC_L11") (pintype "unspecified"))
      (node (ref "U1") (pin "L3") (pinfunction "VSSMIF_L3") (pintype "unspecified"))
      (node (ref "U1") (pin "L5") (pinfunction "VSSLSC_L5") (pintype "unspecified"))
      (node (ref "U1") (pin "L6") (pinfunction "VSSLIF_L6") (pintype "unspecified"))
      (node (ref "U1") (pin "L7") (pinfunction "VSSLIF_L7") (pintype "unspecified"))
      (node (ref "U1") (pin "L8") (pinfunction "VSSLSC_L8") (pintype "unspecified"))
      (node (ref "U1") (pin "M10") (pinfunction "VSSLCN_M10") (pintype "unspecified"))
      (node (ref "U1") (pin "M2") (pinfunction "VSSMIF_M2") (pintype "unspecified"))
      (node (ref "U1") (pin "M3") (pinfunction "VSSMIF_M3") (pintype "unspecified"))
      (node (ref "U1") (pin "M5") (pinfunction "VSSLIF_M5") (pintype "unspecified"))
      (node (ref "U1") (pin "M6") (pinfunction "VSSLIF_M6") (pintype "unspecified"))
      (node (ref "U1") (pin "M7") (pinfunction "VSSLIF_M7") (pintype "unspecified"))
      (node (ref "U1") (pin "M8") (pinfunction "VSSLIF_M8") (pintype "unspecified"))
      (node (ref "U1") (pin "M9") (pinfunction "VSSLIF_M9") (pintype "unspecified"))
      (node (ref "U1") (pin "N3") (pinfunction "VSSLSC_N3") (pintype "unspecified"))
      (node (ref "U2") (pin "2") (pinfunction "GND_2") (pintype "unspecified"))
      (node (ref "U4") (pin "C2") (pinfunction "GND_C2") (pintype "unspecified"))
      (node (ref "U5") (pin "2") (pinfunction "NC_2") (pintype "unspecified"))
      (node (ref "U5") (pin "3") (pinfunction "NC_3") (pintype "unspecified"))
      (node (ref "U5") (pin "5") (pinfunction "GND_5") (pintype "unspecified"))
      (node (ref "U5") (pin "7") (pinfunction "EP_7") (pintype "unspecified"))
      (node (ref "U6") (pin "3") (pinfunction "GND_3") (pintype "unspecified"))
      (node (ref "U6") (pin "4") (pinfunction "INV_4") (pintype "unspecified"))
      (node (ref "X1") (pin "2") (pinfunction "GND_2") (pintype "unspecified"))
    )
    (net (code "10") (name "MIPI1N") (class "Default")
      (node (ref "FPC1") (pin "15") (pinfunction "15_15") (pintype "unspecified"))
      (node (ref "U1") (pin "P6") (pinfunction "DMO1N_P6") (pintype "unspecified"))
    )
    (net (code "11") (name "MIPI1P") (class "Default")
      (node (ref "FPC1") (pin "16") (pinfunction "16_16") (pintype "unspecified"))
      (node (ref "U1") (pin "N6") (pinfunction "DMO1P_N6") (pintype "unspecified"))
    )
    (net (code "12") (name "MIPI2N") (class "Default")
      (node (ref "FPC1") (pin "21") (pinfunction "21_21") (pintype "unspecified"))
      (node (ref "U1") (pin "P8") (pinfunction "DMO2N_P8") (pintype "unspecified"))
    )
    (net (code "13") (name "MIPI2P") (class "Default")
      (node (ref "FPC1") (pin "22") (pinfunction "22_22") (pintype "unspecified"))
      (node (ref "U1") (pin "N8") (pinfunction "DMO2P_N8") (pintype "unspecified"))
    )
    (net (code "14") (name "MIPI3N") (class "Default")
      (node (ref "FPC1") (pin "12") (pinfunction "12_12") (pintype "unspecified"))
      (node (ref "U1") (pin "P5") (pinfunction "DMO3N_P5") (pintype "unspecified"))
    )
    (net (code "15") (name "MIPI3P") (class "Default")
      (node (ref "FPC1") (pin "13") (pinfunction "13_13") (pintype "unspecified"))
      (node (ref "U1") (pin "N5") (pinfunction "DMO3P_N5") (pintype "unspecified"))
    )
    (net (code "16") (name "MIPI4N") (class "Default")
      (node (ref "FPC1") (pin "24") (pinfunction "24_24") (pintype "unspecified"))
      (node (ref "U1") (pin "P9") (pinfunction "DMO4N_P9") (pintype "unspecified"))
    )
    (net (code "17") (name "MIPI4P") (class "Default")
      (node (ref "FPC1") (pin "25") (pinfunction "25_25") (pintype "unspecified"))
      (node (ref "U1") (pin "N9") (pinfunction "DMO4P_N9") (pintype "unspecified"))
    )
    (net (code "18") (name "MIPI_CLK_N") (class "Default")
      (node (ref "FPC1") (pin "18") (pinfunction "18_18") (pintype "unspecified"))
      (node (ref "U1") (pin "P7") (pinfunction "DMCKN_P7") (pintype "unspecified"))
    )
    (net (code "19") (name "MIPI_CLK_P") (class "Default")
      (node (ref "FPC1") (pin "19") (pinfunction "19_19") (pintype "unspecified"))
      (node (ref "U1") (pin "N7") (pinfunction "DMCKP_N7") (pintype "unspecified"))
    )
    (net (code "20") (name "Net-(U1-OMODE)") (class "Default")
      (node (ref "R2") (pin "1") (pinfunction "1_1") (pintype "input"))
      (node (ref "U1") (pin "J10") (pinfunction "OMODE_J10") (pintype "unspecified"))
    )
    (net (code "21") (name "Net-(U1-VBGR)") (class "Default")
      (node (ref "C23") (pin "2") (pinfunction "2_2") (pintype "input"))
      (node (ref "U1") (pin "C11") (pinfunction "VBGR_C11") (pintype "unspecified"))
    )
    (net (code "22") (name "Net-(U1-VRLFR)") (class "Default")
      (node (ref "C5") (pin "2") (pinfunction "2_2") (pintype "input"))
      (node (ref "U1") (pin "A5") (pinfunction "VRLFR_A5") (pintype "unspecified"))
    )
    (net (code "23") (name "Net-(U1-VRLST)") (class "Default")
      (node (ref "C6") (pin "2") (pinfunction "2_2") (pintype "input"))
      (node (ref "U1") (pin "B5") (pinfunction "VRLST_B5") (pintype "unspecified"))
    )
    (net (code "24") (name "Net-(U1-XMASTER)") (class "Default")
      (node (ref "R1") (pin "2") (pinfunction "2_2") (pintype "input"))
      (node (ref "U1") (pin "F11") (pinfunction "XMASTER_F11") (pintype "unspecified"))
    )
    (net (code "25") (name "Net-(U4-SW)") (class "Default")
      (node (ref "L1") (pin "1") (pinfunction "1_1") (pintype "unspecified"))
      (node (ref "U4") (pin "B2") (pinfunction "SW_B2") (pintype "unspecified"))
    )
    (net (code "26") (name "Net-(U6-TADJ)") (class "Default")
      (node (ref "C42") (pin "1") (pinfunction "1_1") (pintype "input"))
      (node (ref "U6") (pin "5") (pinfunction "TADJ_5") (pintype "unspecified"))
    )
    (net (code "27") (name "PWRON") (class "Default")
      (node (ref "FPC1") (pin "1") (pinfunction "1_1") (pintype "unspecified"))
      (node (ref "U6") (pin "2") (pinfunction "EN_2") (pintype "unspecified"))
    )
    (net (code "28") (name "SCK") (class "Default")
      (node (ref "FPC1") (pin "5") (pinfunction "5_5") (pintype "unspecified"))
      (node (ref "U1") (pin "G10") (pinfunction "SCK_G10") (pintype "unspecified"))
    )
    (net (code "29") (name "SDI") (class "Default")
      (node (ref "FPC1") (pin "4") (pinfunction "4_4") (pintype "unspecified"))
      (node (ref "U1") (pin "H10") (pinfunction "SDI_H10") (pintype "unspecified"))
    )
    (net (code "30") (name "XCLR") (class "Default")
      (node (ref "FPC1") (pin "2") (pinfunction "2_2") (pintype "unspecified"))
      (node (ref "U1") (pin "K10") (pinfunction "XCLR_K10") (pintype "unspecified"))
    )
    (net (code "31") (name "unconnected-(SCREW1-Pad1)") (class "Default")
      (node (ref "SCREW1") (pin "1") (pinfunction "1_1") (pintype "input"))
    )
    (net (code "32") (name "unconnected-(SCREW2-Pad1)") (class "Default")
      (node (ref "SCREW2") (pin "1") (pinfunction "1_1") (pintype "input"))
    )
    (net (code "33") (name "unconnected-(SCREW3-Pad1)") (class "Default")
      (node (ref "SCREW3") (pin "1") (pinfunction "1_1") (pintype "input"))
    )
    (net (code "34") (name "unconnected-(SCREW4-Pad1)") (class "Default")
      (node (ref "SCREW4") (pin "1") (pinfunction "1_1") (pintype "input"))
    )
    (net (code "35") (name "unconnected-(SCREW5-Pad1)") (class "Default")
      (node (ref "SCREW5") (pin "1") (pinfunction "1_1") (pintype "input"))
    )
    (net (code "36") (name "unconnected-(SCREW6-Pad1)") (class "Default")
      (node (ref "SCREW6") (pin "1") (pinfunction "1_1") (pintype "input"))
    )
    (net (code "37") (name "unconnected-(U1-DLCKM-PadG1)") (class "Default")
      (node (ref "U1") (pin "G1") (pinfunction "DLCKM_G1") (pintype "unspecified+no_connect"))
    )
    (net (code "38") (name "unconnected-(U1-DLCKP-PadG2)") (class "Default")
      (node (ref "U1") (pin "G2") (pinfunction "DLCKP_G2") (pintype "unspecified+no_connect"))
    )
    (net (code "39") (name "unconnected-(U1-DLOMA-PadC1)") (class "Default")
      (node (ref "U1") (pin "C1") (pinfunction "DLOMA_C1") (pintype "unspecified+no_connect"))
    )
    (net (code "40") (name "unconnected-(U1-DLOMB-PadD1)") (class "Default")
      (node (ref "U1") (pin "D1") (pinfunction "DLOMB_D1") (pintype "unspecified+no_connect"))
    )
    (net (code "41") (name "unconnected-(U1-DLOMC-PadE1)") (class "Default")
      (node (ref "U1") (pin "E1") (pinfunction "DLOMC_E1") (pintype "unspecified"))
    )
    (net (code "42") (name "unconnected-(U1-DLOMD-PadF1)") (class "Default")
      (node (ref "U1") (pin "F1") (pinfunction "DLOMD_F1") (pintype "unspecified+no_connect"))
    )
    (net (code "43") (name "unconnected-(U1-DLOME-PadH1)") (class "Default")
      (node (ref "U1") (pin "H1") (pinfunction "DLOME_H1") (pintype "unspecified+no_connect"))
    )
    (net (code "44") (name "unconnected-(U1-DLOMF-PadJ1)") (class "Default")
      (node (ref "U1") (pin "J1") (pinfunction "DLOMF_J1") (pintype "unspecified+no_connect"))
    )
    (net (code "45") (name "unconnected-(U1-DLOMG-PadK1)") (class "Default")
      (node (ref "U1") (pin "K1") (pinfunction "DLOMG_K1") (pintype "unspecified+no_connect"))
    )
    (net (code "46") (name "unconnected-(U1-DLOMH-PadL1)") (class "Default")
      (node (ref "U1") (pin "L1") (pinfunction "DLOMH_L1") (pintype "unspecified+no_connect"))
    )
    (net (code "47") (name "unconnected-(U1-DLOPA-PadC2)") (class "Default")
      (node (ref "U1") (pin "C2") (pinfunction "DLOPA_C2") (pintype "unspecified+no_connect"))
    )
    (net (code "48") (name "unconnected-(U1-DLOPB-PadD2)") (class "Default")
      (node (ref "U1") (pin "D2") (pinfunction "DLOPB_D2") (pintype "unspecified+no_connect"))
    )
    (net (code "49") (name "unconnected-(U1-DLOPC-PadE2)") (class "Default")
      (node (ref "U1") (pin "E2") (pinfunction "DLOPC_E2") (pintype "unspecified"))
    )
    (net (code "50") (name "unconnected-(U1-DLOPD-PadF2)") (class "Default")
      (node (ref "U1") (pin "F2") (pinfunction "DLOPD_F2") (pintype "unspecified+no_connect"))
    )
    (net (code "51") (name "unconnected-(U1-DLOPE-PadH2)") (class "Default")
      (node (ref "U1") (pin "H2") (pinfunction "DLOPE_H2") (pintype "unspecified+no_connect"))
    )
    (net (code "52") (name "unconnected-(U1-DLOPF-PadJ2)") (class "Default")
      (node (ref "U1") (pin "J2") (pinfunction "DLOPF_J2") (pintype "unspecified+no_connect"))
    )
    (net (code "53") (name "unconnected-(U1-DLOPG-PadK2)") (class "Default")
      (node (ref "U1") (pin "K2") (pinfunction "DLOPG_K2") (pintype "unspecified+no_connect"))
    )
    (net (code "54") (name "unconnected-(U1-DLOPH-PadL2)") (class "Default")
      (node (ref "U1") (pin "L2") (pinfunction "DLOPH_L2") (pintype "unspecified+no_connect"))
    )
    (net (code "55") (name "unconnected-(U1-N.C.-PadA1)") (class "Default")
      (node (ref "U1") (pin "A1") (pinfunction "N.C._A1") (pintype "unspecified+no_connect"))
    )
    (net (code "56") (name "unconnected-(U1-N.C.-PadA11)") (class "Default")
      (node (ref "U1") (pin "A11") (pinfunction "N.C._A11") (pintype "unspecified+no_connect"))
    )
    (net (code "57") (name "unconnected-(U1-N.C.-PadC4)") (class "Default")
      (node (ref "U1") (pin "C4") (pinfunction "N.C._C4") (pintype "unspecified+no_connect"))
    )
    (net (code "58") (name "unconnected-(U1-N.C.-PadC5)") (class "Default")
      (node (ref "U1") (pin "C5") (pinfunction "N.C._C5") (pintype "unspecified+no_connect"))
    )
    (net (code "59") (name "unconnected-(U1-N.C.-PadC6)") (class "Default")
      (node (ref "U1") (pin "C6") (pinfunction "N.C._C6") (pintype "unspecified+no_connect"))
    )
    (net (code "60") (name "unconnected-(U1-N.C.-PadC7)") (class "Default")
      (node (ref "U1") (pin "C7") (pinfunction "N.C._C7") (pintype "unspecified+no_connect"))
    )
    (net (code "61") (name "unconnected-(U1-N.C.-PadC8)") (class "Default")
      (node (ref "U1") (pin "C8") (pinfunction "N.C._C8") (pintype "unspecified+no_connect"))
    )
    (net (code "62") (name "unconnected-(U1-N.C.-PadC9)") (class "Default")
      (node (ref "U1") (pin "C9") (pinfunction "N.C._C9") (pintype "unspecified+no_connect"))
    )
    (net (code "63") (name "unconnected-(U1-N.C.-PadD5)") (class "Default")
      (node (ref "U1") (pin "D5") (pinfunction "N.C._D5") (pintype "unspecified+no_connect"))
    )
    (net (code "64") (name "unconnected-(U1-N.C.-PadD6)") (class "Default")
      (node (ref "U1") (pin "D6") (pinfunction "N.C._D6") (pintype "unspecified+no_connect"))
    )
    (net (code "65") (name "unconnected-(U1-N.C.-PadD7)") (class "Default")
      (node (ref "U1") (pin "D7") (pinfunction "N.C._D7") (pintype "unspecified+no_connect"))
    )
    (net (code "66") (name "unconnected-(U1-N.C.-PadD9)") (class "Default")
      (node (ref "U1") (pin "D9") (pinfunction "N.C._D9") (pintype "unspecified+no_connect"))
    )
    (net (code "67") (name "unconnected-(U1-N.C.-PadE5)") (class "Default")
      (node (ref "U1") (pin "E5") (pinfunction "N.C._E5") (pintype "unspecified+no_connect"))
    )
    (net (code "68") (name "unconnected-(U1-N.C.-PadE6)") (class "Default")
      (node (ref "U1") (pin "E6") (pinfunction "N.C._E6") (pintype "unspecified+no_connect"))
    )
    (net (code "69") (name "unconnected-(U1-N.C.-PadE7)") (class "Default")
      (node (ref "U1") (pin "E7") (pinfunction "N.C._E7") (pintype "unspecified+no_connect"))
    )
    (net (code "70") (name "unconnected-(U1-N.C.-PadE9)") (class "Default")
      (node (ref "U1") (pin "E9") (pinfunction "N.C._E9") (pintype "unspecified+no_connect"))
    )
    (net (code "71") (name "unconnected-(U1-N.C.-PadK4)") (class "Default")
      (node (ref "U1") (pin "K4") (pinfunction "N.C._K4") (pintype "unspecified+no_connect"))
    )
    (net (code "72") (name "unconnected-(U1-N.C.-PadK9)") (class "Default")
      (node (ref "U1") (pin "K9") (pinfunction "N.C._K9") (pintype "unspecified+no_connect"))
    )
    (net (code "73") (name "unconnected-(U1-N.C.-PadL4)") (class "Default")
      (node (ref "U1") (pin "L4") (pinfunction "N.C._L4") (pintype "unspecified+no_connect"))
    )
    (net (code "74") (name "unconnected-(U1-N.C.-PadL9)") (class "Default")
      (node (ref "U1") (pin "L9") (pinfunction "N.C._L9") (pintype "unspecified+no_connect"))
    )
    (net (code "75") (name "unconnected-(U1-N.C.-PadM4)") (class "Default")
      (node (ref "U1") (pin "M4") (pinfunction "N.C._M4") (pintype "unspecified+no_connect"))
    )
    (net (code "76") (name "unconnected-(U1-N.C.-PadN4)") (class "Default")
      (node (ref "U1") (pin "N4") (pinfunction "N.C._N4") (pintype "unspecified+no_connect"))
    )
    (net (code "77") (name "unconnected-(U1-N.C.-PadP1)") (class "Default")
      (node (ref "U1") (pin "P1") (pinfunction "N.C._P1") (pintype "unspecified+no_connect"))
    )
    (net (code "78") (name "unconnected-(U1-N.C.-PadP4)") (class "Default")
      (node (ref "U1") (pin "P4") (pinfunction "N.C._P4") (pintype "unspecified+no_connect"))
    )
    (net (code "79") (name "unconnected-(U1-N.C.-PadP11)") (class "Default")
      (node (ref "U1") (pin "P11") (pinfunction "N.C._P11") (pintype "unspecified+no_connect"))
    )
    (net (code "80") (name "unconnected-(U1-SDO-PadF10)") (class "Default")
      (node (ref "U1") (pin "F10") (pinfunction "SDO_F10") (pintype "unspecified+no_connect"))
    )
    (net (code "81") (name "unconnected-(U1-TAMON-PadC10)") (class "Default")
      (node (ref "U1") (pin "C10") (pinfunction "TAMON_C10") (pintype "unspecified+no_connect"))
    )
    (net (code "82") (name "unconnected-(U1-TENABLE-PadE11)") (class "Default")
      (node (ref "U1") (pin "E11") (pinfunction "TENABLE_E11") (pintype "unspecified+no_connect"))
    )
    (net (code "83") (name "unconnected-(U1-TOUT-PadJ11)") (class "Default")
      (node (ref "U1") (pin "J11") (pinfunction "TOUT_J11") (pintype "unspecified+no_connect"))
    )
    (net (code "84") (name "unconnected-(U1-VLOADLM-PadA3)") (class "Default")
      (node (ref "U1") (pin "A3") (pinfunction "VLOADLM_A3") (pintype "unspecified"))
    )
    (net (code "85") (name "unconnected-(U1-XHS-PadL10)") (class "Default")
      (node (ref "U1") (pin "L10") (pinfunction "XHS_L10") (pintype "unspecified+no_connect"))
    )
    (net (code "86") (name "unconnected-(U1-XTRIG-PadK11)") (class "Default")
      (node (ref "U1") (pin "K11") (pinfunction "XTRIG_K11") (pintype "unspecified+no_connect"))
    )
    (net (code "87") (name "unconnected-(U1-XVS-PadH11)") (class "Default")
      (node (ref "U1") (pin "H11") (pinfunction "XVS_H11") (pintype "unspecified+no_connect"))
    )
    (net (code "88") (name "unconnected-(U2-NC-Pad4)") (class "Default")
      (node (ref "U2") (pin "4") (pinfunction "NC_4") (pintype "unspecified+no_connect"))
    )
  )
)
